# SPinner.net
KiCad netlist of a schematic drawn in EAGLE
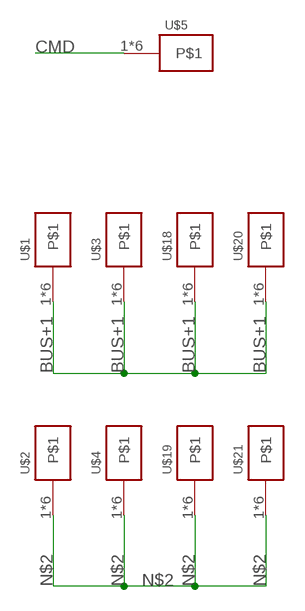
[diagram p0: schematic, sheet 1]

(export (version "E")
  (design (tool "Eeschema 10.0.6"))
  (components
    (comp (ref "U$1")
      (value "KCONNECT")
      (footprint "eagle-import:KCONNECT")
      (libsource (lib "eagle-import") (part "KCONNECT"))
    )
    (comp (ref "U$2")
      (value "KCONNECT")
      (footprint "eagle-import:KCONNECT")
      (libsource (lib "eagle-import") (part "KCONNECT"))
    )
    (comp (ref "U$3")
      (value "KCONNECT")
      (footprint "eagle-import:KCONNECT")
      (libsource (lib "eagle-import") (part "KCONNECT"))
    )
    (comp (ref "U$4")
      (value "KCONNECT")
      (footprint "eagle-import:KCONNECT")
      (libsource (lib "eagle-import") (part "KCONNECT"))
    )
    (comp (ref "U$5")
      (value "KCONNECTQUAD")
      (footprint "eagle-import:KCONNECT_QUAD")
      (libsource (lib "eagle-import") (part "KCONNECTQUAD"))
    )
    (comp (ref "U$18")
      (value "KCONNECT")
      (footprint "eagle-import:KCONNECT")
      (libsource (lib "eagle-import") (part "KCONNECT"))
    )
    (comp (ref "U$19")
      (value "KCONNECT")
      (footprint "eagle-import:KCONNECT")
      (libsource (lib "eagle-import") (part "KCONNECT"))
    )
    (comp (ref "U$20")
      (value "KCONNECT")
      (footprint "eagle-import:KCONNECT")
      (libsource (lib "eagle-import") (part "KCONNECT"))
    )
    (comp (ref "U$21")
      (value "KCONNECT")
      (footprint "eagle-import:KCONNECT")
      (libsource (lib "eagle-import") (part "KCONNECT"))
    )
  )
  (nets
    (net (code "1") (name "/BUS+1") (class "Default")
      (node (ref "U$1") (pin "1") (pinfunction "P$1_1") (pintype "bidirectional"))
      (node (ref "U$1") (pin "2") (pinfunction "P$1_2") (pintype "bidirectional"))
      (node (ref "U$1") (pin "3") (pinfunction "P$1_3") (pintype "bidirectional"))
      (node (ref "U$1") (pin "4") (pinfunction "P$1_4") (pintype "bidirectional"))
      (node (ref "U$1") (pin "P$1") (pinfunction "P$1_P$1") (pintype "bidirectional"))
      (node (ref "U$1") (pin "P$2") (pinfunction "P$1_P$2") (pintype "bidirectional"))
      (node (ref "U$18") (pin "1") (pinfunction "P$1_1") (pintype "bidirectional"))
      (node (ref "U$18") (pin "2") (pinfunction "P$1_2") (pintype "bidirectional"))
      (node (ref "U$18") (pin "3") (pinfunction "P$1_3") (pintype "bidirectional"))
      (node (ref "U$18") (pin "4") (pinfunction "P$1_4") (pintype "bidirectional"))
      (node (ref "U$18") (pin "P$1") (pinfunction "P$1_P$1") (pintype "bidirectional"))
      (node (ref "U$18") (pin "P$2") (pinfunction "P$1_P$2") (pintype "bidirectional"))
      (node (ref "U$20") (pin "1") (pinfunction "P$1_1") (pintype "bidirectional"))
      (node (ref "U$20") (pin "2") (pinfunction "P$1_2") (pintype "bidirectional"))
      (node (ref "U$20") (pin "3") (pinfunction "P$1_3") (pintype "bidirectional"))
      (node (ref "U$20") (pin "4") (pinfunction "P$1_4") (pintype "bidirectional"))
      (node (ref "U$20") (pin "P$1") (pinfunction "P$1_P$1") (pintype "bidirectional"))
      (node (ref "U$20") (pin "P$2") (pinfunction "P$1_P$2") (pintype "bidirectional"))
      (node (ref "U$3") (pin "1") (pinfunction "P$1_1") (pintype "bidirectional"))
      (node (ref "U$3") (pin "2") (pinfunction "P$1_2") (pintype "bidirectional"))
      (node (ref "U$3") (pin "3") (pinfunction "P$1_3") (pintype "bidirectional"))
      (node (ref "U$3") (pin "4") (pinfunction "P$1_4") (pintype "bidirectional"))
      (node (ref "U$3") (pin "P$1") (pinfunction "P$1_P$1") (pintype "bidirectional"))
      (node (ref "U$3") (pin "P$2") (pinfunction "P$1_P$2") (pintype "bidirectional"))
    )
    (net (code "2") (name "/CMD") (class "Default")
      (node (ref "U$5") (pin "1") (pinfunction "P$1_1") (pintype "bidirectional"))
      (node (ref "U$5") (pin "2") (pinfunction "P$1_2") (pintype "bidirectional"))
      (node (ref "U$5") (pin "3") (pinfunction "P$1_3") (pintype "bidirectional"))
      (node (ref "U$5") (pin "4") (pinfunction "P$1_4") (pintype "bidirectional"))
      (node (ref "U$5") (pin "P$1") (pinfunction "P$1_P$1") (pintype "bidirectional"))
      (node (ref "U$5") (pin "P$2") (pinfunction "P$1_P$2") (pintype "bidirectional"))
    )
    (net (code "3") (name "/N$2") (class "Default")
      (node (ref "U$19") (pin "1") (pinfunction "P$1_1") (pintype "bidirectional"))
      (node (ref "U$19") (pin "2") (pinfunction "P$1_2") (pintype "bidirectional"))
      (node (ref "U$19") (pin "3") (pinfunction "P$1_3") (pintype "bidirectional"))
      (node (ref "U$19") (pin "4") (pinfunction "P$1_4") (pintype "bidirectional"))
      (node (ref "U$19") (pin "P$1") (pinfunction "P$1_P$1") (pintype "bidirectional"))
      (node (ref "U$19") (pin "P$2") (pinfunction "P$1_P$2") (pintype "bidirectional"))
      (node (ref "U$2") (pin "1") (pinfunction "P$1_1") (pintype "bidirectional"))
      (node (ref "U$2") (pin "2") (pinfunction "P$1_2") (pintype "bidirectional"))
      (node (ref "U$2") (pin "3") (pinfunction "P$1_3") (pintype "bidirectional"))
      (node (ref "U$2") (pin "4") (pinfunction "P$1_4") (pintype "bidirectional"))
      (node (ref "U$2") (pin "P$1") (pinfunction "P$1_P$1") (pintype "bidirectional"))
      (node (ref "U$2") (pin "P$2") (pinfunction "P$1_P$2") (pintype "bidirectional"))
      (node (ref "U$21") (pin "1") (pinfunction "P$1_1") (pintype "bidirectional"))
      (node (ref "U$21") (pin "2") (pinfunction "P$1_2") (pintype "bidirectional"))
      (node (ref "U$21") (pin "3") (pinfunction "P$1_3") (pintype "bidirectional"))
      (node (ref "U$21") (pin "4") (pinfunction "P$1_4") (pintype "bidirectional"))
      (node (ref "U$21") (pin "P$1") (pinfunction "P$1_P$1") (pintype "bidirectional"))
      (node (ref "U$21") (pin "P$2") (pinfunction "P$1_P$2") (pintype "bidirectional"))
      (node (ref "U$4") (pin "1") (pinfunction "P$1_1") (pintype "bidirectional"))
      (node (ref "U$4") (pin "2") (pinfunction "P$1_2") (pintype "bidirectional"))
      (node (ref "U$4") (pin "3") (pinfunction "P$1_3") (pintype "bidirectional"))
      (node (ref "U$4") (pin "4") (pinfunction "P$1_4") (pintype "bidirectional"))
      (node (ref "U$4") (pin "P$1") (pinfunction "P$1_P$1") (pintype "bidirectional"))
      (node (ref "U$4") (pin "P$2") (pinfunction "P$1_P$2") (pintype "bidirectional"))
    )
  )
)
